# SnapItRev1.net
KiCad netlist of a schematic drawn in Altium Designer
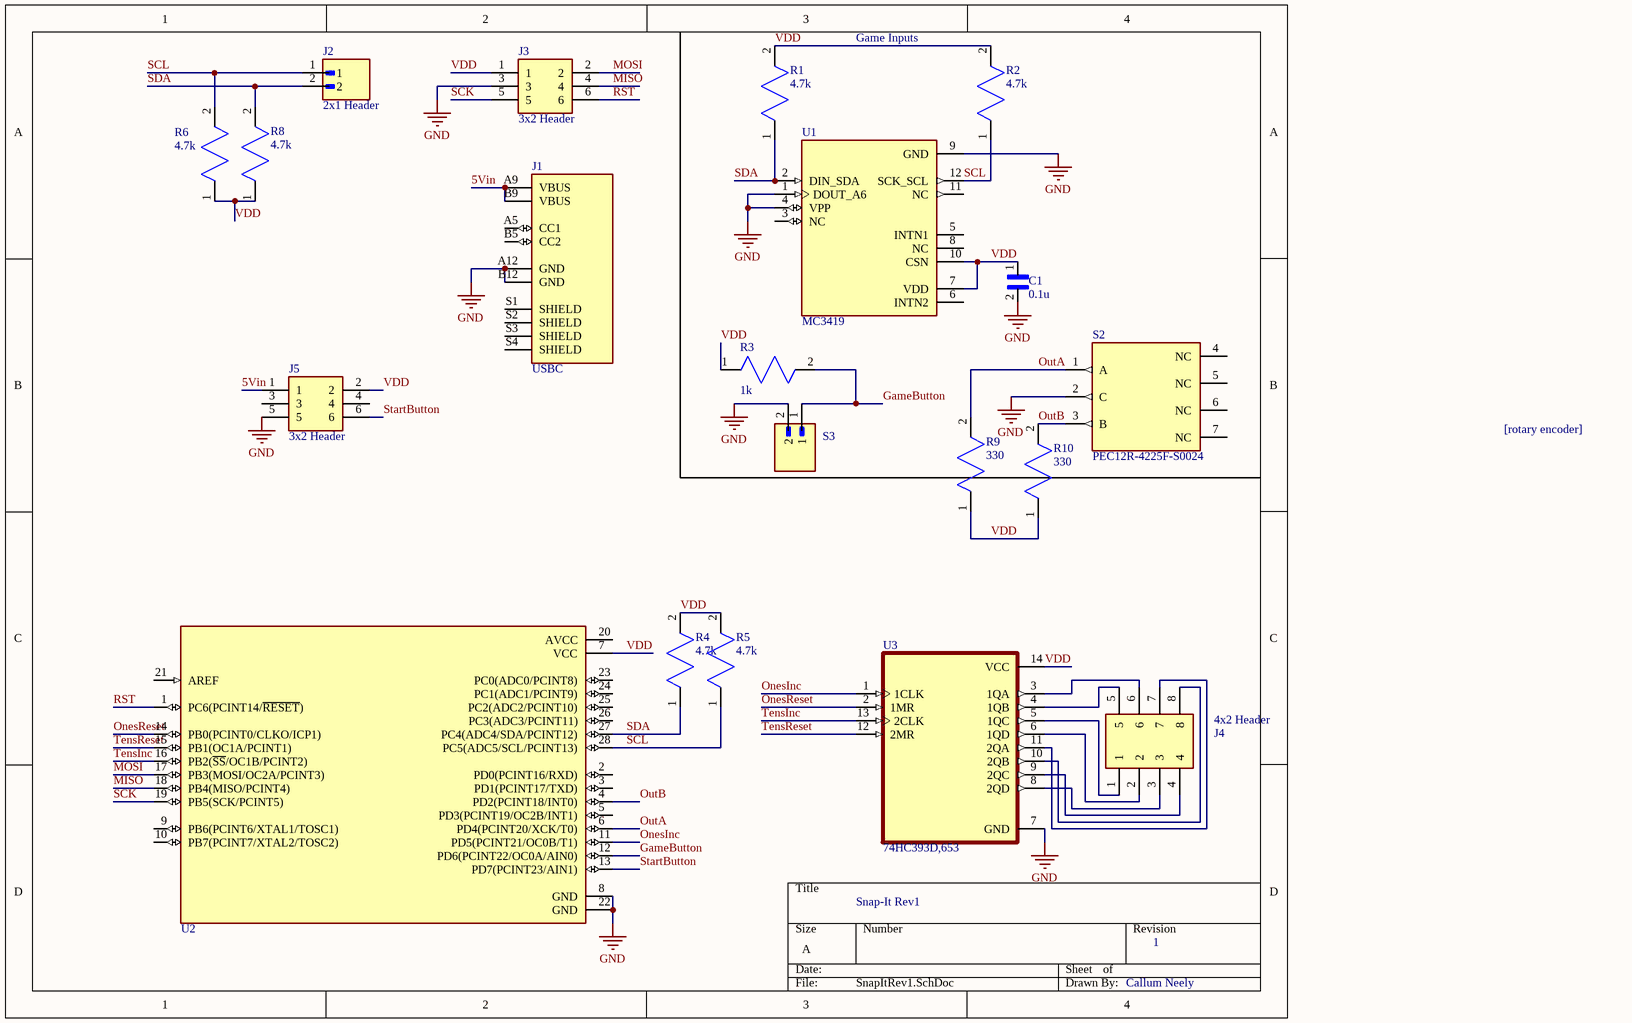
[diagram p0: SnapItRev1.SchDoc]

(export (version "E")
  (design (tool "Eeschema 10.0.6"))
  (components
    (comp (ref "C1") (value "0.1u") (footprint "0402Basic") (libsource (lib "JDLib") (part "CAP")))
    (comp (ref "J1") (value "USBC") (footprint "USBC") (libsource (lib "JDLib") (part "USBC")))
    (comp (ref "J2") (value "2x1 Header") (footprint "2x1 Header") (libsource (lib "") (part "2x1 Header_1")))
    (comp (ref "J3")
      (value "3x2 Header")
      (footprint "3x2 Header")
      (libsource (lib "JDLib") (part "3x2 Header"))
    )
    (comp (ref "J4")
      (value "4x2 Header")
      (footprint "4x2 Header")
      (libsource (lib "JDLib") (part "4x2 Header"))
    )
    (comp (ref "J5")
      (value "3x2 Header")
      (footprint "3x2 Header")
      (libsource (lib "JDLib") (part "3x2 Header"))
    )
    (comp (ref "R1") (value "4.7k") (footprint "0402Basic") (libsource (lib "JDLib") (part "RES")))
    (comp (ref "R2") (value "4.7k") (footprint "0402Basic") (libsource (lib "JDLib") (part "RES")))
    (comp (ref "R3") (value "1k") (footprint "0402Basic") (libsource (lib "JDLib") (part "RES")))
    (comp (ref "R4") (value "4.7k") (footprint "0402Basic") (libsource (lib "JDLib") (part "RES")))
    (comp (ref "R5") (value "4.7k") (footprint "0402Basic") (libsource (lib "JDLib") (part "RES")))
    (comp (ref "R6") (value "4.7k") (footprint "0402Basic") (libsource (lib "JDLib") (part "RES")))
    (comp (ref "R8") (value "4.7k") (footprint "0402Basic") (libsource (lib "JDLib") (part "RES")))
    (comp (ref "R9") (value "330") (footprint "0402Basic") (libsource (lib "JDLib") (part "RES")))
    (comp (ref "R10") (value "330") (footprint "0402Basic") (libsource (lib "JDLib") (part "RES")))
    (comp (ref "S2")
      (value "PEC12R-4225F-S0024")
      (footprint "Rotary Encoder")
      (description "ROTARY ENCODER MECHANICAL 24PPR")
      (libsource (lib "JDLib") (part "PEC12R-4225F-S0024"))
    )
    (comp (ref "S3")
      (value "2x1 Header")
      (footprint "2x1 Header")
      (libsource (lib "JDLib") (part "2x1 Header"))
    )
    (comp (ref "U1")
      (value "MC3419")
      (footprint "12-VFLGA")
      (description "3-AXIS ACCELEROMETER")
      (libsource (lib "JDLib") (part "MC3419"))
    )
    (comp (ref "U2")
      (value "ATMEGA328PU")
      (footprint "ATMEGA328P")
      (libsource (lib "JDLib") (part "ATMEGA328PU"))
    )
    (comp (ref "U3")
      (value "74HC393D,653")
      (footprint "SOIC14 3.9mm")
      (description "4 bit Counter")
      (libsource (lib "JDLib") (part "74HC393D,653"))
    )
  )
  (nets
    (net (code "1") (name "/5Vin") (class "Default")
      (node (ref "J1") (pin "A9") (pinfunction "VBUS_A9") (pintype "power_in"))
      (node (ref "J1") (pin "B9") (pinfunction "VBUS_B9") (pintype "power_in"))
      (node (ref "J5") (pin "1") (pinfunction "1_1") (pintype "passive"))
    )
    (net (code "3") (name "/GameButton") (class "Default")
      (node (ref "R3") (pin "2") (pinfunction "=name_2") (pintype "passive"))
      (node (ref "S3") (pin "1") (pinfunction "1_1") (pintype "passive"))
      (node (ref "U2") (pin "12") (pinfunction "PD6(PCINT22/OC0A/AIN0)_12") (pintype "bidirectional"))
    )
    (net (code "4") (name "/MISO") (class "Default")
      (node (ref "J3") (pin "4") (pinfunction "4_4") (pintype "passive"))
      (node (ref "U2") (pin "18") (pinfunction "PB4(MISO/PCINT4)_18") (pintype "bidirectional"))
    )
    (net (code "5") (name "/MOSI") (class "Default")
      (node (ref "J3") (pin "2") (pinfunction "2_2") (pintype "passive"))
      (node (ref "U2") (pin "17") (pinfunction "PB3(MOSI/OC2A/PCINT3)_17") (pintype "bidirectional"))
    )
    (net (code "6") (name "/OnesInc") (class "Default")
      (node (ref "U2") (pin "11") (pinfunction "PD5(PCINT21/OC0B/T1)_11") (pintype "bidirectional"))
      (node (ref "U3") (pin "1") (pinfunction "1CLK_1") (pintype "input"))
    )
    (net (code "7") (name "/OnesReset") (class "Default")
      (node (ref "U2") (pin "14") (pinfunction "PB0(PCINT0/CLKO/ICP1)_14") (pintype "bidirectional"))
      (node (ref "U3") (pin "2") (pinfunction "1MR_2") (pintype "input"))
    )
    (net (code "8") (name "/OutA") (class "Default")
      (node (ref "R9") (pin "2") (pinfunction "=name_2") (pintype "passive"))
      (node (ref "S2") (pin "1") (pinfunction "A_1") (pintype "output"))
      (node (ref "U2") (pin "6") (pinfunction "PD4(PCINT20/XCK/T0)_6") (pintype "bidirectional"))
    )
    (net (code "9") (name "/OutB") (class "Default")
      (node (ref "R10") (pin "2") (pinfunction "=name_2") (pintype "passive"))
      (node (ref "S2") (pin "3") (pinfunction "B_3") (pintype "output"))
      (node (ref "U2") (pin "4") (pinfunction "PD2(PCINT18/INT0)_4") (pintype "bidirectional"))
    )
    (net (code "10") (name "/RST") (class "Default")
      (node (ref "J3") (pin "6") (pinfunction "6_6") (pintype "passive"))
      (node (ref "U2") (pin "1") (pinfunction "PC6(PCINT14/~{RESET})_1") (pintype "bidirectional"))
    )
    (net (code "11") (name "/SCK") (class "Default")
      (node (ref "J3") (pin "5") (pinfunction "5_5") (pintype "passive"))
      (node (ref "U2") (pin "19") (pinfunction "PB5(SCK/PCINT5)_19") (pintype "bidirectional"))
    )
    (net (code "12") (name "/SCL") (class "Default")
      (node (ref "J2") (pin "1") (pinfunction "1_1") (pintype "passive"))
      (node (ref "R2") (pin "1") (pinfunction "=name_1") (pintype "passive"))
      (node (ref "R5") (pin "1") (pinfunction "=name_1") (pintype "passive"))
      (node (ref "R6") (pin "2") (pinfunction "=name_2") (pintype "passive"))
      (node (ref "U1") (pin "12") (pinfunction "SCK_SCL_12") (pintype "output"))
      (node (ref "U2") (pin "28") (pinfunction "PC5(ADC5/SCL/PCINT13)_28") (pintype "bidirectional"))
    )
    (net (code "13") (name "/SDA") (class "Default")
      (node (ref "J2") (pin "2") (pinfunction "2_2") (pintype "passive"))
      (node (ref "R1") (pin "1") (pinfunction "=name_1") (pintype "passive"))
      (node (ref "R4") (pin "1") (pinfunction "=name_1") (pintype "passive"))
      (node (ref "R8") (pin "2") (pinfunction "=name_2") (pintype "passive"))
      (node (ref "U1") (pin "2") (pinfunction "DIN_SDA_2") (pintype "input"))
      (node (ref "U2") (pin "27") (pinfunction "PC4(ADC4/SDA/PCINT12)_27") (pintype "bidirectional"))
    )
    (net (code "14") (name "/StartButton") (class "Default")
      (node (ref "J5") (pin "6") (pinfunction "6_6") (pintype "passive"))
      (node (ref "U2") (pin "13") (pinfunction "PD7(PCINT23/AIN1)_13") (pintype "bidirectional"))
    )
    (net (code "15") (name "/TensInc") (class "Default")
      (node (ref "U2") (pin "16") (pinfunction "PB2(~{SS}/OC1B/PCINT2)_16") (pintype "bidirectional"))
      (node (ref "U3") (pin "13") (pinfunction "2CLK_13") (pintype "input"))
    )
    (net (code "16") (name "/TensReset") (class "Default")
      (node (ref "U2") (pin "15") (pinfunction "PB1(OC1A/PCINT1)_15") (pintype "bidirectional"))
      (node (ref "U3") (pin "12") (pinfunction "2MR_12") (pintype "input"))
    )
    (net (code "17") (name "/VDD") (class "Default")
      (node (ref "C1") (pin "1") (pinfunction "1_1") (pintype "passive"))
      (node (ref "J3") (pin "1") (pinfunction "1_1") (pintype "passive"))
      (node (ref "J5") (pin "2") (pinfunction "2_2") (pintype "passive"))
      (node (ref "R1") (pin "2") (pinfunction "=name_2") (pintype "passive"))
      (node (ref "R10") (pin "1") (pinfunction "=name_1") (pintype "passive"))
      (node (ref "R2") (pin "2") (pinfunction "=name_2") (pintype "passive"))
      (node (ref "R3") (pin "1") (pinfunction "=name_1") (pintype "passive"))
      (node (ref "R4") (pin "2") (pinfunction "=name_2") (pintype "passive"))
      (node (ref "R5") (pin "2") (pinfunction "=name_2") (pintype "passive"))
      (node (ref "R6") (pin "1") (pinfunction "=name_1") (pintype "passive"))
      (node (ref "R8") (pin "1") (pinfunction "=name_1") (pintype "passive"))
      (node (ref "R9") (pin "1") (pinfunction "=name_1") (pintype "passive"))
      (node (ref "U1") (pin "10") (pinfunction "CSN_10") (pintype "passive"))
      (node (ref "U1") (pin "7") (pinfunction "VDD_7") (pintype "passive"))
      (node (ref "U2") (pin "7") (pinfunction "VCC_7") (pintype "power_in"))
      (node (ref "U3") (pin "14") (pinfunction "VCC_14") (pintype "power_in"))
    )
    (net (code "18") (name "GND") (class "Default")
      (node (ref "C1") (pin "2") (pinfunction "2_2") (pintype "passive"))
      (node (ref "J1") (pin "A12") (pinfunction "GND_A12") (pintype "power_in"))
      (node (ref "J1") (pin "B12") (pinfunction "GND_B12") (pintype "power_in"))
      (node (ref "J3") (pin "3") (pinfunction "3_3") (pintype "passive"))
      (node (ref "J5") (pin "5") (pinfunction "5_5") (pintype "passive"))
      (node (ref "S2") (pin "2") (pinfunction "C_2") (pintype "output"))
      (node (ref "S3") (pin "2") (pinfunction "2_2") (pintype "passive"))
      (node (ref "U1") (pin "1") (pinfunction "DOUT_A6_1") (pintype "input"))
      (node (ref "U1") (pin "4") (pinfunction "VPP_4") (pintype "bidirectional"))
      (node (ref "U1") (pin "9") (pinfunction "GND_9") (pintype "power_in"))
      (node (ref "U2") (pin "22") (pinfunction "GND_22") (pintype "power_in"))
      (node (ref "U2") (pin "8") (pinfunction "GND_8") (pintype "power_in"))
      (node (ref "U3") (pin "7") (pinfunction "GND_7") (pintype "power_in"))
    )
    (net (code "19") (name "Net-(U3-1QA)") (class "Default")
      (node (ref "J4") (pin "6") (pinfunction "6_6") (pintype "passive"))
      (node (ref "U3") (pin "3") (pinfunction "1QA_3") (pintype "output"))
    )
    (net (code "20") (name "Net-(U3-1QB)") (class "Default")
      (node (ref "J4") (pin "5") (pinfunction "5_5") (pintype "passive"))
      (node (ref "U3") (pin "4") (pinfunction "1QB_4") (pintype "output"))
    )
    (net (code "21") (name "Net-(U3-1QC)") (class "Default")
      (node (ref "J4") (pin "1") (pinfunction "1_1") (pintype "passive"))
      (node (ref "U3") (pin "5") (pinfunction "1QC_5") (pintype "output"))
    )
    (net (code "22") (name "Net-(U3-1QD)") (class "Default")
      (node (ref "J4") (pin "2") (pinfunction "2_2") (pintype "passive"))
      (node (ref "U3") (pin "6") (pinfunction "1QD_6") (pintype "output"))
    )
    (net (code "23") (name "Net-(U3-2QA)") (class "Default")
      (node (ref "J4") (pin "7") (pinfunction "7_7") (pintype "passive"))
      (node (ref "U3") (pin "11") (pinfunction "2QA_11") (pintype "output"))
    )
    (net (code "24") (name "Net-(U3-2QB)") (class "Default")
      (node (ref "J4") (pin "8") (pinfunction "8_8") (pintype "passive"))
      (node (ref "U3") (pin "10") (pinfunction "2QB_10") (pintype "output"))
    )
    (net (code "25") (name "Net-(U3-2QC)") (class "Default")
      (node (ref "J4") (pin "4") (pinfunction "4_4") (pintype "passive"))
      (node (ref "U3") (pin "9") (pinfunction "2QC_9") (pintype "output"))
    )
    (net (code "26") (name "Net-(U3-2QD)") (class "Default")
      (node (ref "J4") (pin "3") (pinfunction "3_3") (pintype "passive"))
      (node (ref "U3") (pin "8") (pinfunction "2QD_8") (pintype "output"))
    )
    (net (code "27") (name "unconnected-(J1-CC1-PadA5)") (class "Default")
      (node (ref "J1") (pin "A5") (pinfunction "CC1_A5") (pintype "bidirectional"))
    )
    (net (code "28") (name "unconnected-(J1-CC2-PadB5)") (class "Default")
      (node (ref "J1") (pin "B5") (pinfunction "CC2_B5") (pintype "bidirectional"))
    )
    (net (code "29") (name "unconnected-(J1-SHIELD-PadS1)") (class "Default")
      (node (ref "J1") (pin "S1") (pinfunction "SHIELD_S1") (pintype "passive"))
    )
    (net (code "30") (name "unconnected-(J1-SHIELD-PadS2)") (class "Default")
      (node (ref "J1") (pin "S2") (pinfunction "SHIELD_S2") (pintype "passive"))
    )
    (net (code "31") (name "unconnected-(J1-SHIELD-PadS3)") (class "Default")
      (node (ref "J1") (pin "S3") (pinfunction "SHIELD_S3") (pintype "passive"))
    )
    (net (code "32") (name "unconnected-(J1-SHIELD-PadS4)") (class "Default")
      (node (ref "J1") (pin "S4") (pinfunction "SHIELD_S4") (pintype "passive"))
    )
    (net (code "33") (name "unconnected-(J5-Pad3)") (class "Default")
      (node (ref "J5") (pin "3") (pinfunction "3_3") (pintype "passive"))
    )
    (net (code "34") (name "unconnected-(J5-Pad4)") (class "Default")
      (node (ref "J5") (pin "4") (pinfunction "4_4") (pintype "passive"))
    )
    (net (code "35") (name "unconnected-(S2-NC-Pad4)") (class "Default")
      (node (ref "S2") (pin "4") (pinfunction "NC_4") (pintype "passive"))
    )
    (net (code "36") (name "unconnected-(S2-NC-Pad5)") (class "Default")
      (node (ref "S2") (pin "5") (pinfunction "NC_5") (pintype "passive"))
    )
    (net (code "37") (name "unconnected-(S2-NC-Pad6)") (class "Default")
      (node (ref "S2") (pin "6") (pinfunction "NC_6") (pintype "passive"))
    )
    (net (code "38") (name "unconnected-(S2-NC-Pad7)") (class "Default")
      (node (ref "S2") (pin "7") (pinfunction "NC_7") (pintype "passive"))
    )
    (net (code "39") (name "unconnected-(U1-INTN1-Pad5)") (class "Default")
      (node (ref "U1") (pin "5") (pinfunction "INTN1_5") (pintype "passive"))
    )
    (net (code "40") (name "unconnected-(U1-INTN2-Pad6)") (class "Default")
      (node (ref "U1") (pin "6") (pinfunction "INTN2_6") (pintype "power_in"))
    )
    (net (code "41") (name "unconnected-(U1-NC-Pad3)") (class "Default")
      (node (ref "U1") (pin "3") (pinfunction "NC_3") (pintype "bidirectional"))
    )
    (net (code "42") (name "unconnected-(U1-NC-Pad8)") (class "Default")
      (node (ref "U1") (pin "8") (pinfunction "NC_8") (pintype "passive"))
    )
    (net (code "43") (name "unconnected-(U1-NC-Pad11)") (class "Default")
      (node (ref "U1") (pin "11") (pinfunction "NC_11") (pintype "output"))
    )
    (net (code "44") (name "unconnected-(U2-AREF-Pad21)") (class "Default")
      (node (ref "U2") (pin "21") (pinfunction "AREF_21") (pintype "input"))
    )
    (net (code "45") (name "unconnected-(U2-AVCC-Pad20)") (class "Default")
      (node (ref "U2") (pin "20") (pinfunction "AVCC_20") (pintype "power_in"))
    )
    (net (code "46") (name "unconnected-(U2-PB6(PCINT6{slash}XTAL1{slash}TOSC1)-Pad9)") (class "Default")
      (node (ref "U2") (pin "9") (pinfunction "PB6(PCINT6/XTAL1/TOSC1)_9") (pintype "bidirectional"))
    )
    (net (code "47") (name "unconnected-(U2-PB7(PCINT7{slash}XTAL2{slash}TOSC2)-Pad10)") (class "Default")
      (node (ref "U2") (pin "10") (pinfunction "PB7(PCINT7/XTAL2/TOSC2)_10") (pintype "bidirectional"))
    )
    (net (code "48") (name "unconnected-(U2-PC0(ADC0{slash}PCINT8)-Pad23)") (class "Default")
      (node (ref "U2") (pin "23") (pinfunction "PC0(ADC0/PCINT8)_23") (pintype "bidirectional"))
    )
    (net (code "49") (name "unconnected-(U2-PC1(ADC1{slash}PCINT9)-Pad24)") (class "Default")
      (node (ref "U2") (pin "24") (pinfunction "PC1(ADC1/PCINT9)_24") (pintype "bidirectional"))
    )
    (net (code "50") (name "unconnected-(U2-PC2(ADC2{slash}PCINT10)-Pad25)") (class "Default")
      (node (ref "U2") (pin "25") (pinfunction "PC2(ADC2/PCINT10)_25") (pintype "bidirectional"))
    )
    (net (code "51") (name "unconnected-(U2-PC3(ADC3{slash}PCINT11)-Pad26)") (class "Default")
      (node (ref "U2") (pin "26") (pinfunction "PC3(ADC3/PCINT11)_26") (pintype "bidirectional"))
    )
    (net (code "52") (name "unconnected-(U2-PD0(PCINT16{slash}RXD)-Pad2)") (class "Default")
      (node (ref "U2") (pin "2") (pinfunction "PD0(PCINT16/RXD)_2") (pintype "bidirectional"))
    )
    (net (code "53") (name "unconnected-(U2-PD1(PCINT17{slash}TXD)-Pad3)") (class "Default")
      (node (ref "U2") (pin "3") (pinfunction "PD1(PCINT17/TXD)_3") (pintype "bidirectional"))
    )
    (net (code "54") (name "unconnected-(U2-PD3(PCINT19{slash}OC2B{slash}INT1)-Pad5)") (class "Default")
      (node (ref "U2") (pin "5") (pinfunction "PD3(PCINT19/OC2B/INT1)_5") (pintype "bidirectional"))
    )
  )
)
